# TxPCB_V1-1.net
KiCad netlist of a schematic drawn in EAGLE
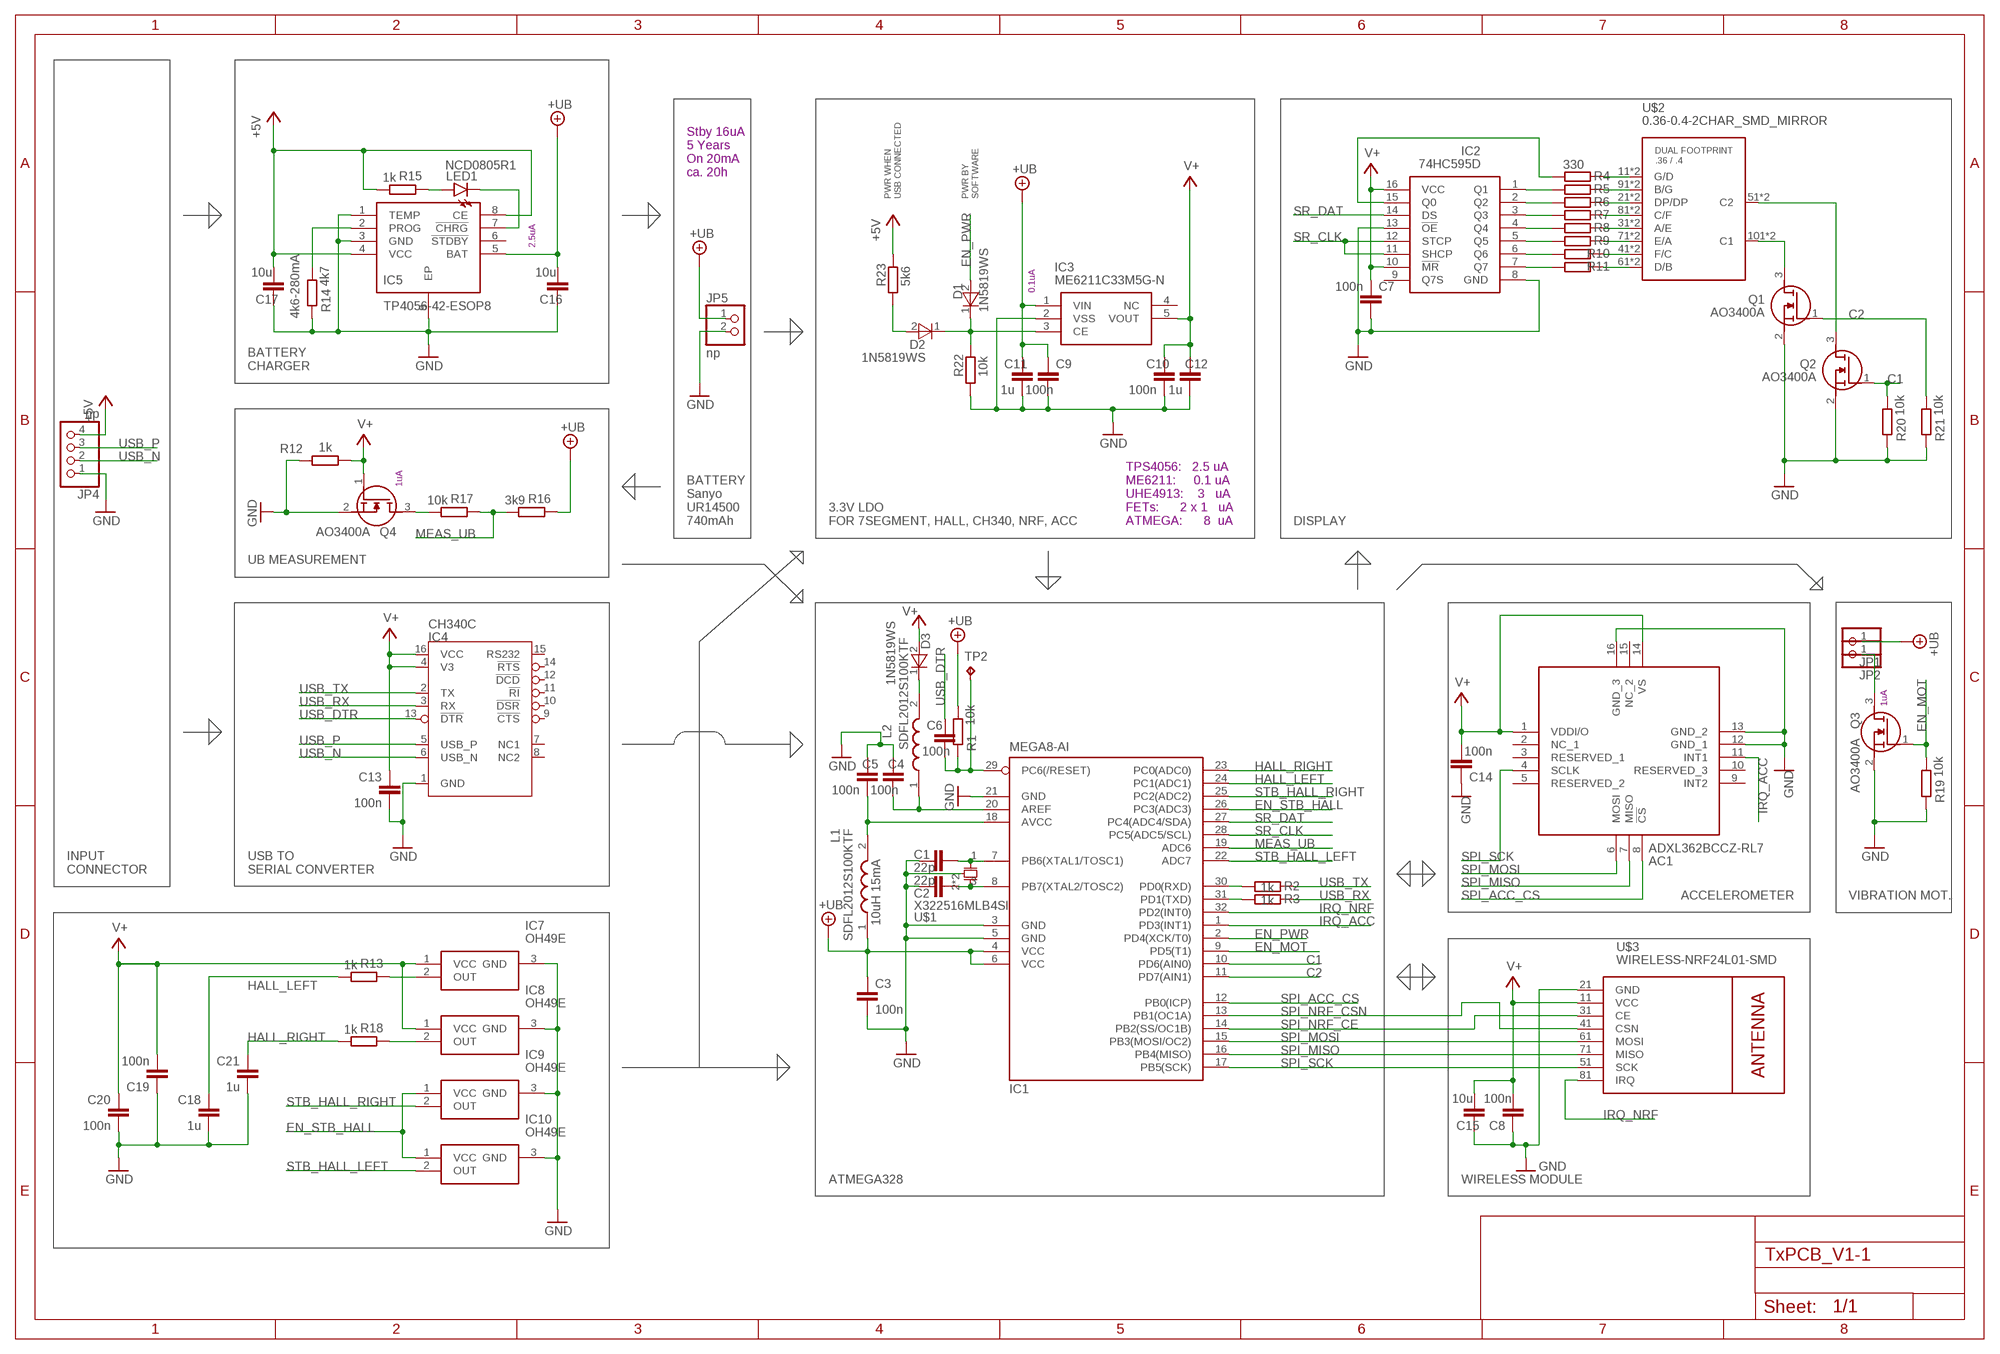
[diagram p0: schematic, sheet 1]

(export (version "E")
  (design (tool "Eeschema 10.0.6"))
  (components
    (comp (ref "AC1")
      (value "ADXL362BCCZ-RL7")
      (footprint "eagle-import:CC-16-4")
      (fields (field (name "MOUSER_PART_NUMBER") "584-ADXL362BCCZ-R7"))
      (libsource (lib "eagle-import") (part "ADXL362BCCZ-RL7"))
    )
    (comp (ref "C1")
      (value "22p")
      (footprint "eagle-import:C0603")
      (libsource (lib "eagle-import") (part "C-EUC0603"))
    )
    (comp (ref "C2")
      (value "22p")
      (footprint "eagle-import:C0603")
      (libsource (lib "eagle-import") (part "C-EUC0603"))
    )
    (comp (ref "C3")
      (value "100n")
      (footprint "eagle-import:C0603")
      (libsource (lib "eagle-import") (part "C-EUC0603"))
    )
    (comp (ref "C4")
      (value "100n")
      (footprint "eagle-import:C0603")
      (libsource (lib "eagle-import") (part "C-EUC0603"))
    )
    (comp (ref "C5")
      (value "100n")
      (footprint "eagle-import:C0603")
      (libsource (lib "eagle-import") (part "C-EUC0603"))
    )
    (comp (ref "C6")
      (value "100n")
      (footprint "eagle-import:C0603")
      (libsource (lib "eagle-import") (part "C-EUC0603"))
    )
    (comp (ref "C7")
      (value "100n")
      (footprint "eagle-import:C0603")
      (libsource (lib "eagle-import") (part "C-EUC0603"))
    )
    (comp (ref "C8")
      (value "100n")
      (footprint "eagle-import:C0603")
      (libsource (lib "eagle-import") (part "C-EUC0603"))
    )
    (comp (ref "C9")
      (value "100n")
      (footprint "eagle-import:C0603")
      (libsource (lib "eagle-import") (part "C-EUC0603"))
    )
    (comp (ref "C10")
      (value "100n")
      (footprint "eagle-import:C0603")
      (libsource (lib "eagle-import") (part "C-EUC0603"))
    )
    (comp (ref "C11")
      (value "1u")
      (footprint "eagle-import:C0603")
      (libsource (lib "eagle-import") (part "C-EUC0603"))
    )
    (comp (ref "C12")
      (value "1u")
      (footprint "eagle-import:C0603")
      (libsource (lib "eagle-import") (part "C-EUC0603"))
    )
    (comp (ref "C13")
      (value "100n")
      (footprint "eagle-import:C0603")
      (libsource (lib "eagle-import") (part "C-EUC0603"))
    )
    (comp (ref "C14")
      (value "100n")
      (footprint "eagle-import:C0603")
      (libsource (lib "eagle-import") (part "C-EUC0603"))
    )
    (comp (ref "C15")
      (value "10u")
      (footprint "eagle-import:C0603")
      (libsource (lib "eagle-import") (part "C-EUC0603"))
    )
    (comp (ref "C16")
      (value "10u")
      (footprint "eagle-import:C0603")
      (libsource (lib "eagle-import") (part "C-EUC0603"))
    )
    (comp (ref "C17")
      (value "10u")
      (footprint "eagle-import:C0603")
      (libsource (lib "eagle-import") (part "C-EUC0603"))
    )
    (comp (ref "C18")
      (value "1u")
      (footprint "eagle-import:C0603")
      (libsource (lib "eagle-import") (part "C-EUC0603"))
    )
    (comp (ref "C19")
      (value "100n")
      (footprint "eagle-import:C0603")
      (libsource (lib "eagle-import") (part "C-EUC0603"))
    )
    (comp (ref "C20")
      (value "100n")
      (footprint "eagle-import:C0603")
      (libsource (lib "eagle-import") (part "C-EUC0603"))
    )
    (comp (ref "C21")
      (value "1u")
      (footprint "eagle-import:C0603")
      (libsource (lib "eagle-import") (part "C-EUC0603"))
    )
    (comp (ref "D1")
      (value "1N5819WS")
      (footprint "eagle-import:SODFL2512X90N")
      (fields
        (field (name "ARROW_PART_NUMBER") "1N4148WS")
        (field (name "MOUSER_PART_NUMBER") "512-1N4148WS")
      )
      (libsource (lib "eagle-import") (part "1N4148WS"))
    )
    (comp (ref "D2")
      (value "1N5819WS")
      (footprint "eagle-import:SODFL2512X90N")
      (fields
        (field (name "ARROW_PART_NUMBER") "1N4148WS")
        (field (name "MOUSER_PART_NUMBER") "512-1N4148WS")
      )
      (libsource (lib "eagle-import") (part "1N4148WS"))
    )
    (comp (ref "D3")
      (value "1N5819WS")
      (footprint "eagle-import:SODFL2512X90N")
      (fields
        (field (name "ARROW_PART_NUMBER") "1N4148WS")
        (field (name "MOUSER_PART_NUMBER") "512-1N4148WS")
      )
      (libsource (lib "eagle-import") (part "1N4148WS"))
    )
    (comp (ref "IC1")
      (value "MEGA8-AI")
      (footprint "eagle-import:TQFP32-08")
      (fields (field (name "MPN") "ATMEGA8-16AU"))
      (libsource (lib "eagle-import") (part "MEGA8-AI"))
    )
    (comp (ref "IC2")
      (value "74HC595D")
      (footprint "eagle-import:SOIC127P600X175-16N")
      (libsource (lib "eagle-import") (part "74HC595D"))
    )
    (comp (ref "IC3")
      (value "ME6211C33M5G-N")
      (footprint "eagle-import:SOT95P282X145-5N")
      (fields (field (name "MANUFACTURER_PART_NUMBER") "ME6211C50M5G"))
      (libsource (lib "eagle-import") (part "ME6211C50M5G"))
    )
    (comp (ref "IC4")
      (value "CH340C")
      (footprint "eagle-import:SOIC16N")
      (libsource (lib "eagle-import") (part "CH340G"))
    )
    (comp (ref "IC5")
      (value "TP4056-42-ESOP8")
      (footprint "eagle-import:SOIC127P600X175-9N")
      (libsource (lib "eagle-import") (part "TP4056-42-ESOP8"))
    )
    (comp (ref "IC7")
      (value "OH49E")
      (footprint "eagle-import:SOT95P237X112-3N")
      (fields
        (field (name "ARROW_PART_NUMBER") "DRV5055A3QDBZR")
        (field (name "MOUSER_PART_NUMBER") "595-DRV5055A3QDBZR")
      )
      (libsource (lib "eagle-import") (part "DRV5055A3QDBZR"))
    )
    (comp (ref "IC8")
      (value "OH49E")
      (footprint "eagle-import:SOT95P237X112-3N")
      (fields
        (field (name "ARROW_PART_NUMBER") "DRV5055A3QDBZR")
        (field (name "MOUSER_PART_NUMBER") "595-DRV5055A3QDBZR")
      )
      (libsource (lib "eagle-import") (part "DRV5055A3QDBZR"))
    )
    (comp (ref "IC9")
      (value "OH49E")
      (footprint "eagle-import:SOT95P237X112-3N")
      (fields
        (field (name "ARROW_PART_NUMBER") "DRV5055A3QDBZR")
        (field (name "MOUSER_PART_NUMBER") "595-DRV5055A3QDBZR")
      )
      (libsource (lib "eagle-import") (part "DRV5055A3QDBZR"))
    )
    (comp (ref "IC10")
      (value "OH49E")
      (footprint "eagle-import:SOT95P237X112-3N")
      (fields
        (field (name "ARROW_PART_NUMBER") "DRV5055A3QDBZR")
        (field (name "MOUSER_PART_NUMBER") "595-DRV5055A3QDBZR")
      )
      (libsource (lib "eagle-import") (part "DRV5055A3QDBZR"))
    )
    (comp (ref "JP1")
      (value "PINHD-1X1")
      (footprint "eagle-import:1X01")
      (libsource (lib "eagle-import") (part "PINHD-1X1"))
    )
    (comp (ref "JP2")
      (value "PINHD-1X1")
      (footprint "eagle-import:1X01")
      (libsource (lib "eagle-import") (part "PINHD-1X1"))
    )
    (comp (ref "JP4")
      (value "np")
      (footprint "eagle-import:1X04")
      (libsource (lib "eagle-import") (part "PINHD-1X4"))
    )
    (comp (ref "JP5")
      (value "np")
      (footprint "eagle-import:1X02")
      (libsource (lib "eagle-import") (part "PINHD-1X2"))
    )
    (comp (ref "L1")
      (value "SDFL2012S100KTF")
      (footprint "eagle-import:INDC2112X105N")
      (fields (field (name "MANUFACTURER_PART_NUMBER") "SDFL2012Q2R7KTF"))
      (libsource (lib "eagle-import") (part "SDFL2012Q2R7KTF"))
    )
    (comp (ref "L2")
      (value "SDFL2012S100KTF")
      (footprint "eagle-import:INDC2112X105N")
      (fields (field (name "MANUFACTURER_PART_NUMBER") "SDFL2012Q2R7KTF"))
      (libsource (lib "eagle-import") (part "SDFL2012Q2R7KTF"))
    )
    (comp (ref "LED1")
      (value "NCD0805R1")
      (footprint "eagle-import:CHIP-LED0805")
      (libsource (lib "eagle-import") (part "LEDCHIP-LED0805"))
    )
    (comp (ref "Q1")
      (value "AO3400A")
      (footprint "eagle-import:SOT95P280X125-3N")
      (libsource (lib "eagle-import") (part "AO3400A"))
    )
    (comp (ref "Q2")
      (value "AO3400A")
      (footprint "eagle-import:SOT95P280X125-3N")
      (libsource (lib "eagle-import") (part "AO3400A"))
    )
    (comp (ref "Q3")
      (value "AO3400A")
      (footprint "eagle-import:SOT95P280X125-3N")
      (libsource (lib "eagle-import") (part "AO3400A"))
    )
    (comp (ref "Q4")
      (value "AO3400A")
      (footprint "eagle-import:SOT95P280X125-3N")
      (libsource (lib "eagle-import") (part "AO3400A"))
    )
    (comp (ref "R1")
      (value "10k")
      (footprint "eagle-import:R0603")
      (libsource (lib "eagle-import") (part "R-EU_R0603"))
    )
    (comp (ref "R2")
      (value "1k")
      (footprint "eagle-import:R0603")
      (libsource (lib "eagle-import") (part "R-EU_R0603"))
    )
    (comp (ref "R3")
      (value "1k")
      (footprint "eagle-import:R0603")
      (libsource (lib "eagle-import") (part "R-EU_R0603"))
    )
    (comp (ref "R4")
      (value "330")
      (footprint "eagle-import:R0603")
      (libsource (lib "eagle-import") (part "R-EU_R0603"))
    )
    (comp (ref "R5")
      (value "330")
      (footprint "eagle-import:R0603")
      (libsource (lib "eagle-import") (part "R-EU_R0603"))
    )
    (comp (ref "R6")
      (value "330")
      (footprint "eagle-import:R0603")
      (libsource (lib "eagle-import") (part "R-EU_R0603"))
    )
    (comp (ref "R7")
      (value "330")
      (footprint "eagle-import:R0603")
      (libsource (lib "eagle-import") (part "R-EU_R0603"))
    )
    (comp (ref "R8")
      (value "330")
      (footprint "eagle-import:R0603")
      (libsource (lib "eagle-import") (part "R-EU_R0603"))
    )
    (comp (ref "R9")
      (value "330")
      (footprint "eagle-import:R0603")
      (libsource (lib "eagle-import") (part "R-EU_R0603"))
    )
    (comp (ref "R10")
      (value "330")
      (footprint "eagle-import:R0603")
      (libsource (lib "eagle-import") (part "R-EU_R0603"))
    )
    (comp (ref "R11")
      (value "330")
      (footprint "eagle-import:R0603")
      (libsource (lib "eagle-import") (part "R-EU_R0603"))
    )
    (comp (ref "R12")
      (value "1k")
      (footprint "eagle-import:R0603")
      (libsource (lib "eagle-import") (part "R-EU_R0603"))
    )
    (comp (ref "R13")
      (value "1k")
      (footprint "eagle-import:R0603")
      (libsource (lib "eagle-import") (part "R-EU_R0603"))
    )
    (comp (ref "R14")
      (value "4k7")
      (footprint "eagle-import:R0603")
      (libsource (lib "eagle-import") (part "R-EU_R0603"))
    )
    (comp (ref "R15")
      (value "1k")
      (footprint "eagle-import:R0603")
      (libsource (lib "eagle-import") (part "R-EU_R0603"))
    )
    (comp (ref "R16")
      (value "3k9")
      (footprint "eagle-import:R0603")
      (libsource (lib "eagle-import") (part "R-EU_R0603"))
    )
    (comp (ref "R17")
      (value "10k")
      (footprint "eagle-import:R0603")
      (libsource (lib "eagle-import") (part "R-EU_R0603"))
    )
    (comp (ref "R18")
      (value "1k")
      (footprint "eagle-import:R0603")
      (libsource (lib "eagle-import") (part "R-EU_R0603"))
    )
    (comp (ref "R19")
      (value "10k")
      (footprint "eagle-import:R0603")
      (libsource (lib "eagle-import") (part "R-EU_R0603"))
    )
    (comp (ref "R20")
      (value "10k")
      (footprint "eagle-import:R0603")
      (libsource (lib "eagle-import") (part "R-EU_R0603"))
    )
    (comp (ref "R21")
      (value "10k")
      (footprint "eagle-import:R0603")
      (libsource (lib "eagle-import") (part "R-EU_R0603"))
    )
    (comp (ref "R22")
      (value "10k")
      (footprint "eagle-import:R0603")
      (libsource (lib "eagle-import") (part "R-EU_R0603"))
    )
    (comp (ref "R23")
      (value "5k6")
      (footprint "eagle-import:R0603")
      (libsource (lib "eagle-import") (part "R-EU_R0603"))
    )
    (comp (ref "TP2")
      (value "TPB1,27")
      (footprint "eagle-import:B1,27")
      (libsource (lib "eagle-import") (part "TPB1,27"))
    )
    (comp (ref "U$1")
      (value "X322516MLB4SI")
      (footprint "eagle-import:X322516MLB4SI")
      (libsource (lib "eagle-import") (part "X322516_BETTER"))
    )
    (comp (ref "U$2")
      (value "0.36-0.4-2CHAR_SMD_MIRROR")
      (footprint "eagle-import:COMBO-036-04_SMD")
      (libsource (lib "eagle-import") (part "0.36-0.4-2CHAR_SMD_MIRROR"))
    )
    (comp (ref "U$3")
      (value "WIRELESS-NRF24L01-SMD")
      (footprint "eagle-import:WIRELESS-NRF24L01_SMD")
      (libsource (lib "eagle-import") (part "WIRELESS-NRF24L01-SMD"))
    )
  )
  (nets
    (net (code "1") (name "+5V") (class "Default")
      (node (ref "C17") (pin "1") (pinfunction "1_1") (pintype "passive"))
      (node (ref "IC5") (pin "4") (pinfunction "VCC_4") (pintype "bidirectional"))
      (node (ref "IC5") (pin "8") (pinfunction "CE_8") (pintype "bidirectional"))
      (node (ref "JP4") (pin "4") (pinfunction "4_4") (pintype "passive"))
      (node (ref "R15") (pin "2") (pinfunction "2_2") (pintype "passive"))
      (node (ref "R23") (pin "2") (pinfunction "2_2") (pintype "passive"))
    )
    (net (code "2") (name "+UB") (class "Default")
      (node (ref "C11") (pin "1") (pinfunction "1_1") (pintype "passive"))
      (node (ref "C16") (pin "1") (pinfunction "1_1") (pintype "passive"))
      (node (ref "C3") (pin "1") (pinfunction "1_1") (pintype "passive"))
      (node (ref "C9") (pin "1") (pinfunction "1_1") (pintype "passive"))
      (node (ref "IC1") (pin "4") (pinfunction "VCC_4") (pintype "power_in"))
      (node (ref "IC1") (pin "6") (pinfunction "VCC_6") (pintype "power_in"))
      (node (ref "IC3") (pin "1") (pinfunction "VIN_1") (pintype "bidirectional"))
      (node (ref "IC5") (pin "5") (pinfunction "BAT_5") (pintype "bidirectional"))
      (node (ref "JP1") (pin "1") (pinfunction "1_1") (pintype "passive"))
      (node (ref "JP5") (pin "1") (pinfunction "1_1") (pintype "passive"))
      (node (ref "L1") (pin "1") (pinfunction "1_1") (pintype "bidirectional"))
      (node (ref "R1") (pin "2") (pinfunction "2_2") (pintype "passive"))
      (node (ref "R16") (pin "1") (pinfunction "1_1") (pintype "passive"))
    )
    (net (code "3") (name "/C1") (class "Default")
      (node (ref "IC1") (pin "10") (pinfunction "PD6(AIN0)_10") (pintype "bidirectional"))
      (node (ref "Q2") (pin "1") (pinfunction "G_1") (pintype "bidirectional"))
      (node (ref "R20") (pin "2") (pinfunction "2_2") (pintype "passive"))
    )
    (net (code "4") (name "/C2") (class "Default")
      (node (ref "IC1") (pin "11") (pinfunction "PD7(AIN1)_11") (pintype "bidirectional"))
      (node (ref "Q1") (pin "1") (pinfunction "G_1") (pintype "bidirectional"))
      (node (ref "R21") (pin "2") (pinfunction "2_2") (pintype "passive"))
    )
    (net (code "5") (name "/EN_MOT") (class "Default")
      (node (ref "IC1") (pin "9") (pinfunction "PD5(T1)_9") (pintype "bidirectional"))
      (node (ref "Q3") (pin "1") (pinfunction "G_1") (pintype "bidirectional"))
      (node (ref "R19") (pin "2") (pinfunction "2_2") (pintype "passive"))
    )
    (net (code "6") (name "/EN_PWR") (class "Default")
      (node (ref "D1") (pin "2") (pinfunction "A_2") (pintype "bidirectional"))
      (node (ref "IC1") (pin "2") (pinfunction "PD4(XCK/T0)_2") (pintype "bidirectional"))
    )
    (net (code "7") (name "/EN_STB_HALL") (class "Default")
      (node (ref "IC1") (pin "26") (pinfunction "PC3(ADC3)_26") (pintype "bidirectional"))
      (node (ref "IC10") (pin "1") (pinfunction "VCC_1") (pintype "bidirectional"))
      (node (ref "IC9") (pin "1") (pinfunction "VCC_1") (pintype "bidirectional"))
    )
    (net (code "8") (name "/HALL_LEFT") (class "Default")
      (node (ref "C18") (pin "1") (pinfunction "1_1") (pintype "passive"))
      (node (ref "IC1") (pin "24") (pinfunction "PC1(ADC1)_24") (pintype "bidirectional"))
      (node (ref "R13") (pin "2") (pinfunction "2_2") (pintype "passive"))
    )
    (net (code "9") (name "/HALL_RIGHT") (class "Default")
      (node (ref "C21") (pin "1") (pinfunction "1_1") (pintype "passive"))
      (node (ref "IC1") (pin "23") (pinfunction "PC0(ADC0)_23") (pintype "bidirectional"))
      (node (ref "R18") (pin "2") (pinfunction "2_2") (pintype "passive"))
    )
    (net (code "10") (name "/IRQ_ACC") (class "Default")
      (node (ref "AC1") (pin "11") (pinfunction "INT1_11") (pintype "input"))
      (node (ref "IC1") (pin "1") (pinfunction "PD3(INT1)_1") (pintype "bidirectional"))
    )
    (net (code "11") (name "/IRQ_NRF") (class "Default")
      (node (ref "IC1") (pin "32") (pinfunction "PD2(INT0)_32") (pintype "bidirectional"))
      (node (ref "U$3") (pin "81") (pinfunction "IRQ_81") (pintype "bidirectional"))
    )
    (net (code "12") (name "/MEAS_UB") (class "Default")
      (node (ref "IC1") (pin "19") (pinfunction "ADC6_19") (pintype "bidirectional"))
      (node (ref "R16") (pin "2") (pinfunction "2_2") (pintype "passive"))
      (node (ref "R17") (pin "1") (pinfunction "1_1") (pintype "passive"))
    )
    (net (code "13") (name "/SPI_ACC_CS") (class "Default")
      (node (ref "AC1") (pin "8") (pinfunction "~{CS}_8") (pintype "input"))
      (node (ref "IC1") (pin "12") (pinfunction "PB0(ICP)_12") (pintype "bidirectional"))
    )
    (net (code "14") (name "/SPI_MISO") (class "Default")
      (node (ref "AC1") (pin "7") (pinfunction "MISO_7") (pintype "bidirectional"))
      (node (ref "IC1") (pin "16") (pinfunction "PB4(MISO)_16") (pintype "bidirectional"))
      (node (ref "U$3") (pin "71") (pinfunction "MISO_71") (pintype "bidirectional"))
    )
    (net (code "15") (name "/SPI_MOSI") (class "Default")
      (node (ref "AC1") (pin "6") (pinfunction "MOSI_6") (pintype "bidirectional"))
      (node (ref "IC1") (pin "15") (pinfunction "PB3(MOSI/OC2)_15") (pintype "bidirectional"))
      (node (ref "U$3") (pin "61") (pinfunction "MOSI_61") (pintype "bidirectional"))
    )
    (net (code "16") (name "/SPI_NRF_CE") (class "Default")
      (node (ref "IC1") (pin "14") (pinfunction "PB2(SS/OC1B)_14") (pintype "bidirectional"))
      (node (ref "U$3") (pin "31") (pinfunction "CE_31") (pintype "bidirectional"))
    )
    (net (code "17") (name "/SPI_NRF_CSN") (class "Default")
      (node (ref "IC1") (pin "13") (pinfunction "PB1(OC1A)_13") (pintype "bidirectional"))
      (node (ref "U$3") (pin "41") (pinfunction "CSN_41") (pintype "bidirectional"))
    )
    (net (code "18") (name "/SPI_SCK") (class "Default")
      (node (ref "AC1") (pin "4") (pinfunction "SCLK_4") (pintype "input"))
      (node (ref "IC1") (pin "17") (pinfunction "PB5(SCK)_17") (pintype "bidirectional"))
      (node (ref "U$3") (pin "51") (pinfunction "SCK_51") (pintype "bidirectional"))
    )
    (net (code "19") (name "/SR_CLK") (class "Default")
      (node (ref "IC1") (pin "28") (pinfunction "PC5(ADC5/SCL)_28") (pintype "bidirectional"))
      (node (ref "IC2") (pin "11") (pinfunction "SHCP_11") (pintype "bidirectional"))
      (node (ref "IC2") (pin "12") (pinfunction "STCP_12") (pintype "bidirectional"))
    )
    (net (code "20") (name "/SR_DAT") (class "Default")
      (node (ref "IC1") (pin "27") (pinfunction "PC4(ADC4/SDA)_27") (pintype "bidirectional"))
      (node (ref "IC2") (pin "14") (pinfunction "DS_14") (pintype "bidirectional"))
    )
    (net (code "21") (name "/STB_HALL_LEFT") (class "Default")
      (node (ref "IC1") (pin "22") (pinfunction "ADC7_22") (pintype "bidirectional"))
      (node (ref "IC10") (pin "2") (pinfunction "OUT_2") (pintype "bidirectional"))
    )
    (net (code "22") (name "/STB_HALL_RIGHT") (class "Default")
      (node (ref "IC1") (pin "25") (pinfunction "PC2(ADC2)_25") (pintype "bidirectional"))
      (node (ref "IC9") (pin "2") (pinfunction "OUT_2") (pintype "bidirectional"))
    )
    (net (code "23") (name "/USB_DTR") (class "Default")
      (node (ref "C6") (pin "1") (pinfunction "1_1") (pintype "passive"))
      (node (ref "IC4") (pin "13") (pinfunction "~{DTR}_13") (pintype "output"))
    )
    (net (code "24") (name "/USB_N") (class "Default")
      (node (ref "IC4") (pin "6") (pinfunction "USB_N_6") (pintype "bidirectional"))
      (node (ref "JP4") (pin "2") (pinfunction "2_2") (pintype "passive"))
    )
    (net (code "25") (name "/USB_P") (class "Default")
      (node (ref "IC4") (pin "5") (pinfunction "USB_P_5") (pintype "bidirectional"))
      (node (ref "JP4") (pin "3") (pinfunction "3_3") (pintype "passive"))
    )
    (net (code "26") (name "/USB_RX") (class "Default")
      (node (ref "IC4") (pin "3") (pinfunction "RX_3") (pintype "input"))
      (node (ref "R3") (pin "1") (pinfunction "1_1") (pintype "passive"))
    )
    (net (code "27") (name "/USB_TX") (class "Default")
      (node (ref "IC4") (pin "2") (pinfunction "TX_2") (pintype "output"))
      (node (ref "R2") (pin "1") (pinfunction "1_1") (pintype "passive"))
    )
    (net (code "28") (name "GND") (class "Default")
      (node (ref "AC1") (pin "12") (pinfunction "GND_1_12") (pintype "power_in"))
      (node (ref "AC1") (pin "13") (pinfunction "GND_2_13") (pintype "power_in"))
      (node (ref "AC1") (pin "16") (pinfunction "GND_3_16") (pintype "power_in"))
      (node (ref "C1") (pin "2") (pinfunction "2_2") (pintype "passive"))
      (node (ref "C10") (pin "2") (pinfunction "2_2") (pintype "passive"))
      (node (ref "C11") (pin "2") (pinfunction "2_2") (pintype "passive"))
      (node (ref "C12") (pin "2") (pinfunction "2_2") (pintype "passive"))
      (node (ref "C13") (pin "2") (pinfunction "2_2") (pintype "passive"))
      (node (ref "C14") (pin "1") (pinfunction "1_1") (pintype "passive"))
      (node (ref "C15") (pin "2") (pinfunction "2_2") (pintype "passive"))
      (node (ref "C16") (pin "2") (pinfunction "2_2") (pintype "passive"))
      (node (ref "C17") (pin "2") (pinfunction "2_2") (pintype "passive"))
      (node (ref "C18") (pin "2") (pinfunction "2_2") (pintype "passive"))
      (node (ref "C19") (pin "1") (pinfunction "1_1") (pintype "passive"))
      (node (ref "C2") (pin "2") (pinfunction "2_2") (pintype "passive"))
      (node (ref "C20") (pin "2") (pinfunction "2_2") (pintype "passive"))
      (node (ref "C21") (pin "2") (pinfunction "2_2") (pintype "passive"))
      (node (ref "C3") (pin "2") (pinfunction "2_2") (pintype "passive"))
      (node (ref "C4") (pin "1") (pinfunction "1_1") (pintype "passive"))
      (node (ref "C5") (pin "1") (pinfunction "1_1") (pintype "passive"))
      (node (ref "C7") (pin "2") (pinfunction "2_2") (pintype "passive"))
      (node (ref "C8") (pin "1") (pinfunction "1_1") (pintype "passive"))
      (node (ref "C9") (pin "2") (pinfunction "2_2") (pintype "passive"))
      (node (ref "IC1") (pin "21") (pinfunction "GND_21") (pintype "power_in"))
      (node (ref "IC1") (pin "3") (pinfunction "GND_3") (pintype "power_in"))
      (node (ref "IC1") (pin "5") (pinfunction "GND_5") (pintype "power_in"))
      (node (ref "IC10") (pin "3") (pinfunction "GND_3") (pintype "bidirectional"))
      (node (ref "IC2") (pin "13") (pinfunction "~{OE}_13") (pintype "bidirectional"))
      (node (ref "IC2") (pin "8") (pinfunction "GND_8") (pintype "bidirectional"))
      (node (ref "IC3") (pin "2") (pinfunction "VSS_2") (pintype "bidirectional"))
      (node (ref "IC4") (pin "1") (pinfunction "GND_1") (pintype "input"))
      (node (ref "IC5") (pin "1") (pinfunction "TEMP_1") (pintype "bidirectional"))
      (node (ref "IC5") (pin "3") (pinfunction "GND_3") (pintype "bidirectional"))
      (node (ref "IC5") (pin "9") (pinfunction "EP_9") (pintype "bidirectional"))
      (node (ref "IC7") (pin "3") (pinfunction "GND_3") (pintype "bidirectional"))
      (node (ref "IC8") (pin "3") (pinfunction "GND_3") (pintype "bidirectional"))
      (node (ref "IC9") (pin "3") (pinfunction "GND_3") (pintype "bidirectional"))
      (node (ref "JP4") (pin "1") (pinfunction "1_1") (pintype "passive"))
      (node (ref "JP5") (pin "2") (pinfunction "2_2") (pintype "passive"))
      (node (ref "Q1") (pin "2") (pinfunction "S_2") (pintype "bidirectional"))
      (node (ref "Q2") (pin "2") (pinfunction "S_2") (pintype "bidirectional"))
      (node (ref "Q3") (pin "2") (pinfunction "S_2") (pintype "bidirectional"))
      (node (ref "Q4") (pin "2") (pinfunction "S_2") (pintype "bidirectional"))
      (node (ref "R12") (pin "1") (pinfunction "1_1") (pintype "passive"))
      (node (ref "R14") (pin "1") (pinfunction "1_1") (pintype "passive"))
      (node (ref "R19") (pin "1") (pinfunction "1_1") (pintype "passive"))
      (node (ref "R20") (pin "1") (pinfunction "1_1") (pintype "passive"))
      (node (ref "R21") (pin "1") (pinfunction "1_1") (pintype "passive"))
      (node (ref "R22") (pin "1") (pinfunction "1_1") (pintype "passive"))
      (node (ref "U$1") (pin "2") (pinfunction "G_2") (pintype "bidirectional"))
      (node (ref "U$1") (pin "4") (pinfunction "G_4") (pintype "bidirectional"))
      (node (ref "U$3") (pin "21") (pinfunction "GND_21") (pintype "power_in"))
    )
    (net (code "29") (name "Net-(D1-K)") (class "Default")
      (node (ref "D1") (pin "1") (pinfunction "K_1") (pintype "bidirectional"))
      (node (ref "D2") (pin "1") (pinfunction "K_1") (pintype "bidirectional"))
      (node (ref "IC3") (pin "3") (pinfunction "CE_3") (pintype "bidirectional"))
      (node (ref "R22") (pin "2") (pinfunction "2_2") (pintype "passive"))
    )
    (net (code "30") (name "Net-(D2-A)") (class "Default")
      (node (ref "D2") (pin "2") (pinfunction "A_2") (pintype "bidirectional"))
      (node (ref "R23") (pin "1") (pinfunction "1_1") (pintype "passive"))
    )
    (net (code "31") (name "Net-(D3-K)") (class "Default")
      (node (ref "D3") (pin "1") (pinfunction "K_1") (pintype "bidirectional"))
      (node (ref "L2") (pin "2") (pinfunction "2_2") (pintype "bidirectional"))
    )
    (net (code "32") (name "Net-(IC1-AREF)") (class "Default")
      (node (ref "C4") (pin "2") (pinfunction "2_2") (pintype "passive"))
      (node (ref "IC1") (pin "20") (pinfunction "AREF_20") (pintype "passive"))
      (node (ref "L2") (pin "1") (pinfunction "1_1") (pintype "bidirectional"))
    )
    (net (code "33") (name "Net-(IC1-AVCC)") (class "Default")
      (node (ref "C5") (pin "2") (pinfunction "2_2") (pintype "passive"))
      (node (ref "IC1") (pin "18") (pinfunction "AVCC_18") (pintype "power_in"))
      (node (ref "L1") (pin "2") (pinfunction "2_2") (pintype "bidirectional"))
    )
    (net (code "34") (name "Net-(IC1-PB6(XTAL1{slash}TOSC1))") (class "Default")
      (node (ref "C1") (pin "1") (pinfunction "1_1") (pintype "passive"))
      (node (ref "IC1") (pin "7") (pinfunction "PB6(XTAL1/TOSC1)_7") (pintype "bidirectional"))
      (node (ref "U$1") (pin "1") (pinfunction "X1_1") (pintype "bidirectional"))
    )
    (net (code "35") (name "Net-(IC1-PB7(XTAL2{slash}TOSC2))") (class "Default")
      (node (ref "C2") (pin "1") (pinfunction "1_1") (pintype "passive"))
      (node (ref "IC1") (pin "8") (pinfunction "PB7(XTAL2/TOSC2)_8") (pintype "bidirectional"))
      (node (ref "U$1") (pin "3") (pinfunction "X2_3") (pintype "bidirectional"))
    )
    (net (code "36") (name "Net-(IC1-PC6({slash}RESET))") (class "Default")
      (node (ref "C6") (pin "2") (pinfunction "2_2") (pintype "passive"))
      (node (ref "IC1") (pin "29") (pinfunction "PC6(/RESET)_29") (pintype "bidirectional"))
      (node (ref "R1") (pin "1") (pinfunction "1_1") (pintype "passive"))
      (node (ref "TP2") (pin "TP") (pinfunction "TP_TP") (pintype "input"))
    )
    (net (code "37") (name "Net-(IC1-PD0(RXD))") (class "Default")
      (node (ref "IC1") (pin "30") (pinfunction "PD0(RXD)_30") (pintype "bidirectional"))
      (node (ref "R2") (pin "2") (pinfunction "2_2") (pintype "passive"))
    )
    (net (code "38") (name "Net-(IC1-PD1(TXD))") (class "Default")
      (node (ref "IC1") (pin "31") (pinfunction "PD1(TXD)_31") (pintype "bidirectional"))
      (node (ref "R3") (pin "2") (pinfunction "2_2") (pintype "passive"))
    )
    (net (code "39") (name "Net-(IC2-Q0)") (class "Default")
      (node (ref "IC2") (pin "15") (pinfunction "Q0_15") (pintype "bidirectional"))
      (node (ref "R4") (pin "2") (pinfunction "2_2") (pintype "passive"))
    )
    (net (code "40") (name "Net-(IC2-Q1)") (class "Default")
      (node (ref "IC2") (pin "1") (pinfunction "Q1_1") (pintype "bidirectional"))
      (node (ref "R5") (pin "2") (pinfunction "2_2") (pintype "passive"))
    )
    (net (code "41") (name "Net-(IC2-Q2)") (class "Default")
      (node (ref "IC2") (pin "2") (pinfunction "Q2_2") (pintype "bidirectional"))
      (node (ref "R6") (pin "2") (pinfunction "2_2") (pintype "passive"))
    )
    (net (code "42") (name "Net-(IC2-Q3)") (class "Default")
      (node (ref "IC2") (pin "3") (pinfunction "Q3_3") (pintype "bidirectional"))
      (node (ref "R7") (pin "2") (pinfunction "2_2") (pintype "passive"))
    )
    (net (code "43") (name "Net-(IC2-Q4)") (class "Default")
      (node (ref "IC2") (pin "4") (pinfunction "Q4_4") (pintype "bidirectional"))
      (node (ref "R8") (pin "2") (pinfunction "2_2") (pintype "passive"))
    )
    (net (code "44") (name "Net-(IC2-Q5)") (class "Default")
      (node (ref "IC2") (pin "5") (pinfunction "Q5_5") (pintype "bidirectional"))
      (node (ref "R9") (pin "2") (pinfunction "2_2") (pintype "passive"))
    )
    (net (code "45") (name "Net-(IC2-Q6)") (class "Default")
      (node (ref "IC2") (pin "6") (pinfunction "Q6_6") (pintype "bidirectional"))
      (node (ref "R10") (pin "2") (pinfunction "2_2") (pintype "passive"))
    )
    (net (code "46") (name "Net-(IC2-Q7)") (class "Default")
      (node (ref "IC2") (pin "7") (pinfunction "Q7_7") (pintype "bidirectional"))
      (node (ref "R11") (pin "2") (pinfunction "2_2") (pintype "passive"))
    )
    (net (code "47") (name "Net-(IC5-PROG)") (class "Default")
      (node (ref "IC5") (pin "2") (pinfunction "PROG_2") (pintype "bidirectional"))
      (node (ref "R14") (pin "2") (pinfunction "2_2") (pintype "passive"))
    )
    (net (code "48") (name "Net-(IC5-~{CHRG})") (class "Default")
      (node (ref "IC5") (pin "7") (pinfunction "~{CHRG}_7") (pintype "bidirectional"))
      (node (ref "LED1") (pin "C") (pinfunction "C_C") (pintype "passive"))
    )
    (net (code "49") (name "Net-(IC7-OUT)") (class "Default")
      (node (ref "IC7") (pin "2") (pinfunction "OUT_2") (pintype "bidirectional"))
      (node (ref "R13") (pin "1") (pinfunction "1_1") (pintype "passive"))
    )
    (net (code "50") (name "Net-(IC8-OUT)") (class "Default")
      (node (ref "IC8") (pin "2") (pinfunction "OUT_2") (pintype "bidirectional"))
      (node (ref "R18") (pin "1") (pinfunction "1_1") (pintype "passive"))
    )
    (net (code "51") (name "Net-(LED1-PadA)") (class "Default")
      (node (ref "LED1") (pin "A") (pinfunction "A_A") (pintype "passive"))
      (node (ref "R15") (pin "1") (pinfunction "1_1") (pintype "passive"))
    )
    (net (code "52") (name "Net-(Q1-D)") (class "Default")
      (node (ref "Q1") (pin "3") (pinfunction "D_3") (pintype "bidirectional"))
      (node (ref "U$2") (pin "101") (pinfunction "C1_101") (pintype "bidirectional"))
      (node (ref "U$2") (pin "102") (pinfunction "C1_102") (pintype "bidirectional"))
    )
    (net (code "53") (name "Net-(Q2-D)") (class "Default")
      (node (ref "Q2") (pin "3") (pinfunction "D_3") (pintype "bidirectional"))
      (node (ref "U$2") (pin "51") (pinfunction "C2_51") (pintype "bidirectional"))
      (node (ref "U$2") (pin "52") (pinfunction "C2_52") (pintype "bidirectional"))
    )
    (net (code "54") (name "Net-(Q3-D)") (class "Default")
      (node (ref "JP2") (pin "1") (pinfunction "1_1") (pintype "passive"))
      (node (ref "Q3") (pin "3") (pinfunction "D_3") (pintype "bidirectional"))
    )
    (net (code "55") (name "Net-(Q4-D)") (class "Default")
      (node (ref "Q4") (pin "3") (pinfunction "D_3") (pintype "bidirectional"))
      (node (ref "R17") (pin "2") (pinfunction "2_2") (pintype "passive"))
    )
    (net (code "56") (name "Net-(R4-Pad1)") (class "Default")
      (node (ref "R4") (pin "1") (pinfunction "1_1") (pintype "passive"))
      (node (ref "U$2") (pin "11") (pinfunction "G/D_11") (pintype "bidirectional"))
      (node (ref "U$2") (pin "12") (pinfunction "G/D_12") (pintype "bidirectional"))
    )
    (net (code "57") (name "Net-(R5-Pad1)") (class "Default")
      (node (ref "R5") (pin "1") (pinfunction "1_1") (pintype "passive"))
      (node (ref "U$2") (pin "91") (pinfunction "B/G_91") (pintype "bidirectional"))
      (node (ref "U$2") (pin "92") (pinfunction "B/G_92") (pintype "bidirectional"))
    )
    (net (code "58") (name "Net-(R6-Pad1)") (class "Default")
      (node (ref "R6") (pin "1") (pinfunction "1_1") (pintype "passive"))
      (node (ref "U$2") (pin "21") (pinfunction "DP/DP_21") (pintype "bidirectional"))
      (node (ref "U$2") (pin "22") (pinfunction "DP/DP_22") (pintype "bidirectional"))
    )
    (net (code "59") (name "Net-(R7-Pad1)") (class "Default")
      (node (ref "R7") (pin "1") (pinfunction "1_1") (pintype "passive"))
      (node (ref "U$2") (pin "81") (pinfunction "C/F_81") (pintype "bidirectional"))
      (node (ref "U$2") (pin "82") (pinfunction "C/F_82") (pintype "bidirectional"))
    )
    (net (code "60") (name "Net-(R8-Pad1)") (class "Default")
      (node (ref "R8") (pin "1") (pinfunction "1_1") (pintype "passive"))
      (node (ref "U$2") (pin "31") (pinfunction "A/E_31") (pintype "bidirectional"))
      (node (ref "U$2") (pin "32") (pinfunction "A/E_32") (pintype "bidirectional"))
    )
    (net (code "61") (name "Net-(R9-Pad1)") (class "Default")
      (node (ref "R9") (pin "1") (pinfunction "1_1") (pintype "passive"))
      (node (ref "U$2") (pin "71") (pinfunction "E/A_71") (pintype "bidirectional"))
      (node (ref "U$2") (pin "72") (pinfunction "E/A_72") (pintype "bidirectional"))
    )
    (net (code "62") (name "Net-(R10-Pad1)") (class "Default")
      (node (ref "R10") (pin "1") (pinfunction "1_1") (pintype "passive"))
      (node (ref "U$2") (pin "41") (pinfunction "F/C_41") (pintype "bidirectional"))
      (node (ref "U$2") (pin "42") (pinfunction "F/C_42") (pintype "bidirectional"))
    )
    (net (code "63") (name "Net-(R11-Pad1)") (class "Default")
      (node (ref "R11") (pin "1") (pinfunction "1_1") (pintype "passive"))
      (node (ref "U$2") (pin "61") (pinfunction "D/B_61") (pintype "bidirectional"))
      (node (ref "U$2") (pin "62") (pinfunction "D/B_62") (pintype "bidirectional"))
    )
    (net (code "64") (name "V+") (class "Default")
      (node (ref "AC1") (pin "1") (pinfunction "VDDI/O_1") (pintype "power_in"))
      (node (ref "AC1") (pin "14") (pinfunction "VS_14") (pintype "bidirectional"))
      (node (ref "C10") (pin "1") (pinfunction "1_1") (pintype "passive"))
      (node (ref "C12") (pin "1") (pinfunction "1_1") (pintype "passive"))
      (node (ref "C13") (pin "1") (pinfunction "1_1") (pintype "passive"))
      (node (ref "C14") (pin "2") (pinfunction "2_2") (pintype "passive"))
      (node (ref "C15") (pin "1") (pinfunction "1_1") (pintype "passive"))
      (node (ref "C19") (pin "2") (pinfunction "2_2") (pintype "passive"))
      (node (ref "C20") (pin "1") (pinfunction "1_1") (pintype "passive"))
      (node (ref "C7") (pin "1") (pinfunction "1_1") (pintype "passive"))
      (node (ref "C8") (pin "2") (pinfunction "2_2") (pintype "passive"))
      (node (ref "D3") (pin "2") (pinfunction "A_2") (pintype "bidirectional"))
      (node (ref "IC2") (pin "10") (pinfunction "~{MR}_10") (pintype "bidirectional"))
      (node (ref "IC2") (pin "16") (pinfunction "VCC_16") (pintype "bidirectional"))
      (node (ref "IC3") (pin "5") (pinfunction "VOUT_5") (pintype "bidirectional"))
      (node (ref "IC4") (pin "16") (pinfunction "VCC_16") (pintype "input"))
      (node (ref "IC4") (pin "4") (pinfunction "V3_4") (pintype "output"))
      (node (ref "IC7") (pin "1") (pinfunction "VCC_1") (pintype "bidirectional"))
      (node (ref "IC8") (pin "1") (pinfunction "VCC_1") (pintype "bidirectional"))
      (node (ref "Q4") (pin "1") (pinfunction "G_1") (pintype "bidirectional"))
      (node (ref "R12") (pin "2") (pinfunction "2_2") (pintype "passive"))
      (node (ref "U$3") (pin "11") (pinfunction "VCC_11") (pintype "power_in"))
    )
    (net (code "65") (name "unconnected-(AC1-INT2-Pad9)") (class "Default")
      (node (ref "AC1") (pin "9") (pinfunction "INT2_9") (pintype "input"))
    )
    (net (code "66") (name "unconnected-(AC1-NC_1-Pad2)") (class "Default")
      (node (ref "AC1") (pin "2") (pinfunction "NC_1_2") (pintype "bidirectional"))
    )
    (net (code "67") (name "unconnected-(AC1-NC_2-Pad15)") (class "Default")
      (node (ref "AC1") (pin "15") (pinfunction "NC_2_15") (pintype "bidirectional"))
    )
    (net (code "68") (name "unconnected-(AC1-RESERVED_1-Pad3)") (class "Default")
      (node (ref "AC1") (pin "3") (pinfunction "RESERVED_1_3") (pintype "bidirectional"))
    )
    (net (code "69") (name "unconnected-(AC1-RESERVED_2-Pad5)") (class "Default")
      (node (ref "AC1") (pin "5") (pinfunction "RESERVED_2_5") (pintype "bidirectional"))
    )
    (net (code "70") (name "unconnected-(AC1-RESERVED_3-Pad10)") (class "Default")
      (node (ref "AC1") (pin "10") (pinfunction "RESERVED_3_10") (pintype "bidirectional"))
    )
    (net (code "71") (name "unconnected-(IC2-Q7S-Pad9)") (class "Default")
      (node (ref "IC2") (pin "9") (pinfunction "Q7S_9") (pintype "bidirectional"))
    )
    (net (code "72") (name "unconnected-(IC3-NC-Pad4)") (class "Default")
      (node (ref "IC3") (pin "4") (pinfunction "NC_4") (pintype "no_connect"))
    )
    (net (code "73") (name "unconnected-(IC4-NC1-Pad7)") (class "Default")
      (node (ref "IC4") (pin "7") (pinfunction "NC1_7") (pintype "no_connect"))
    )
    (net (code "74") (name "unconnected-(IC4-NC2-Pad8)") (class "Default")
      (node (ref "IC4") (pin "8") (pinfunction "NC2_8") (pintype "no_connect"))
    )
    (net (code "75") (name "unconnected-(IC4-RS232-Pad15)") (class "Default")
      (node (ref "IC4") (pin "15") (pinfunction "RS232_15") (pintype "input"))
    )
    (net (code "76") (name "unconnected-(IC4-~{CTS}-Pad9)") (class "Default")
      (node (ref "IC4") (pin "9") (pinfunction "~{CTS}_9") (pintype "input"))
    )
    (net (code "77") (name "unconnected-(IC4-~{DCD}-Pad12)") (class "Default")
      (node (ref "IC4") (pin "12") (pinfunction "~{DCD}_12") (pintype "input"))
    )
    (net (code "78") (name "unconnected-(IC4-~{DSR}-Pad10)") (class "Default")
      (node (ref "IC4") (pin "10") (pinfunction "~{DSR}_10") (pintype "input"))
    )
    (net (code "79") (name "unconnected-(IC4-~{RI}-Pad11)") (class "Default")
      (node (ref "IC4") (pin "11") (pinfunction "~{RI}_11") (pintype "input"))
    )
    (net (code "80") (name "unconnected-(IC4-~{RTS}-Pad14)") (class "Default")
      (node (ref "IC4") (pin "14") (pinfunction "~{RTS}_14") (pintype "output"))
    )
    (net (code "81") (name "unconnected-(IC5-~{STDBY}-Pad6)") (class "Default")
      (node (ref "IC5") (pin "6") (pinfunction "~{STDBY}_6") (pintype "bidirectional"))
    )
  )
)
